# EVK-IRIS-W1_MOD.net
KiCad netlist of a schematic drawn in Altium Designer
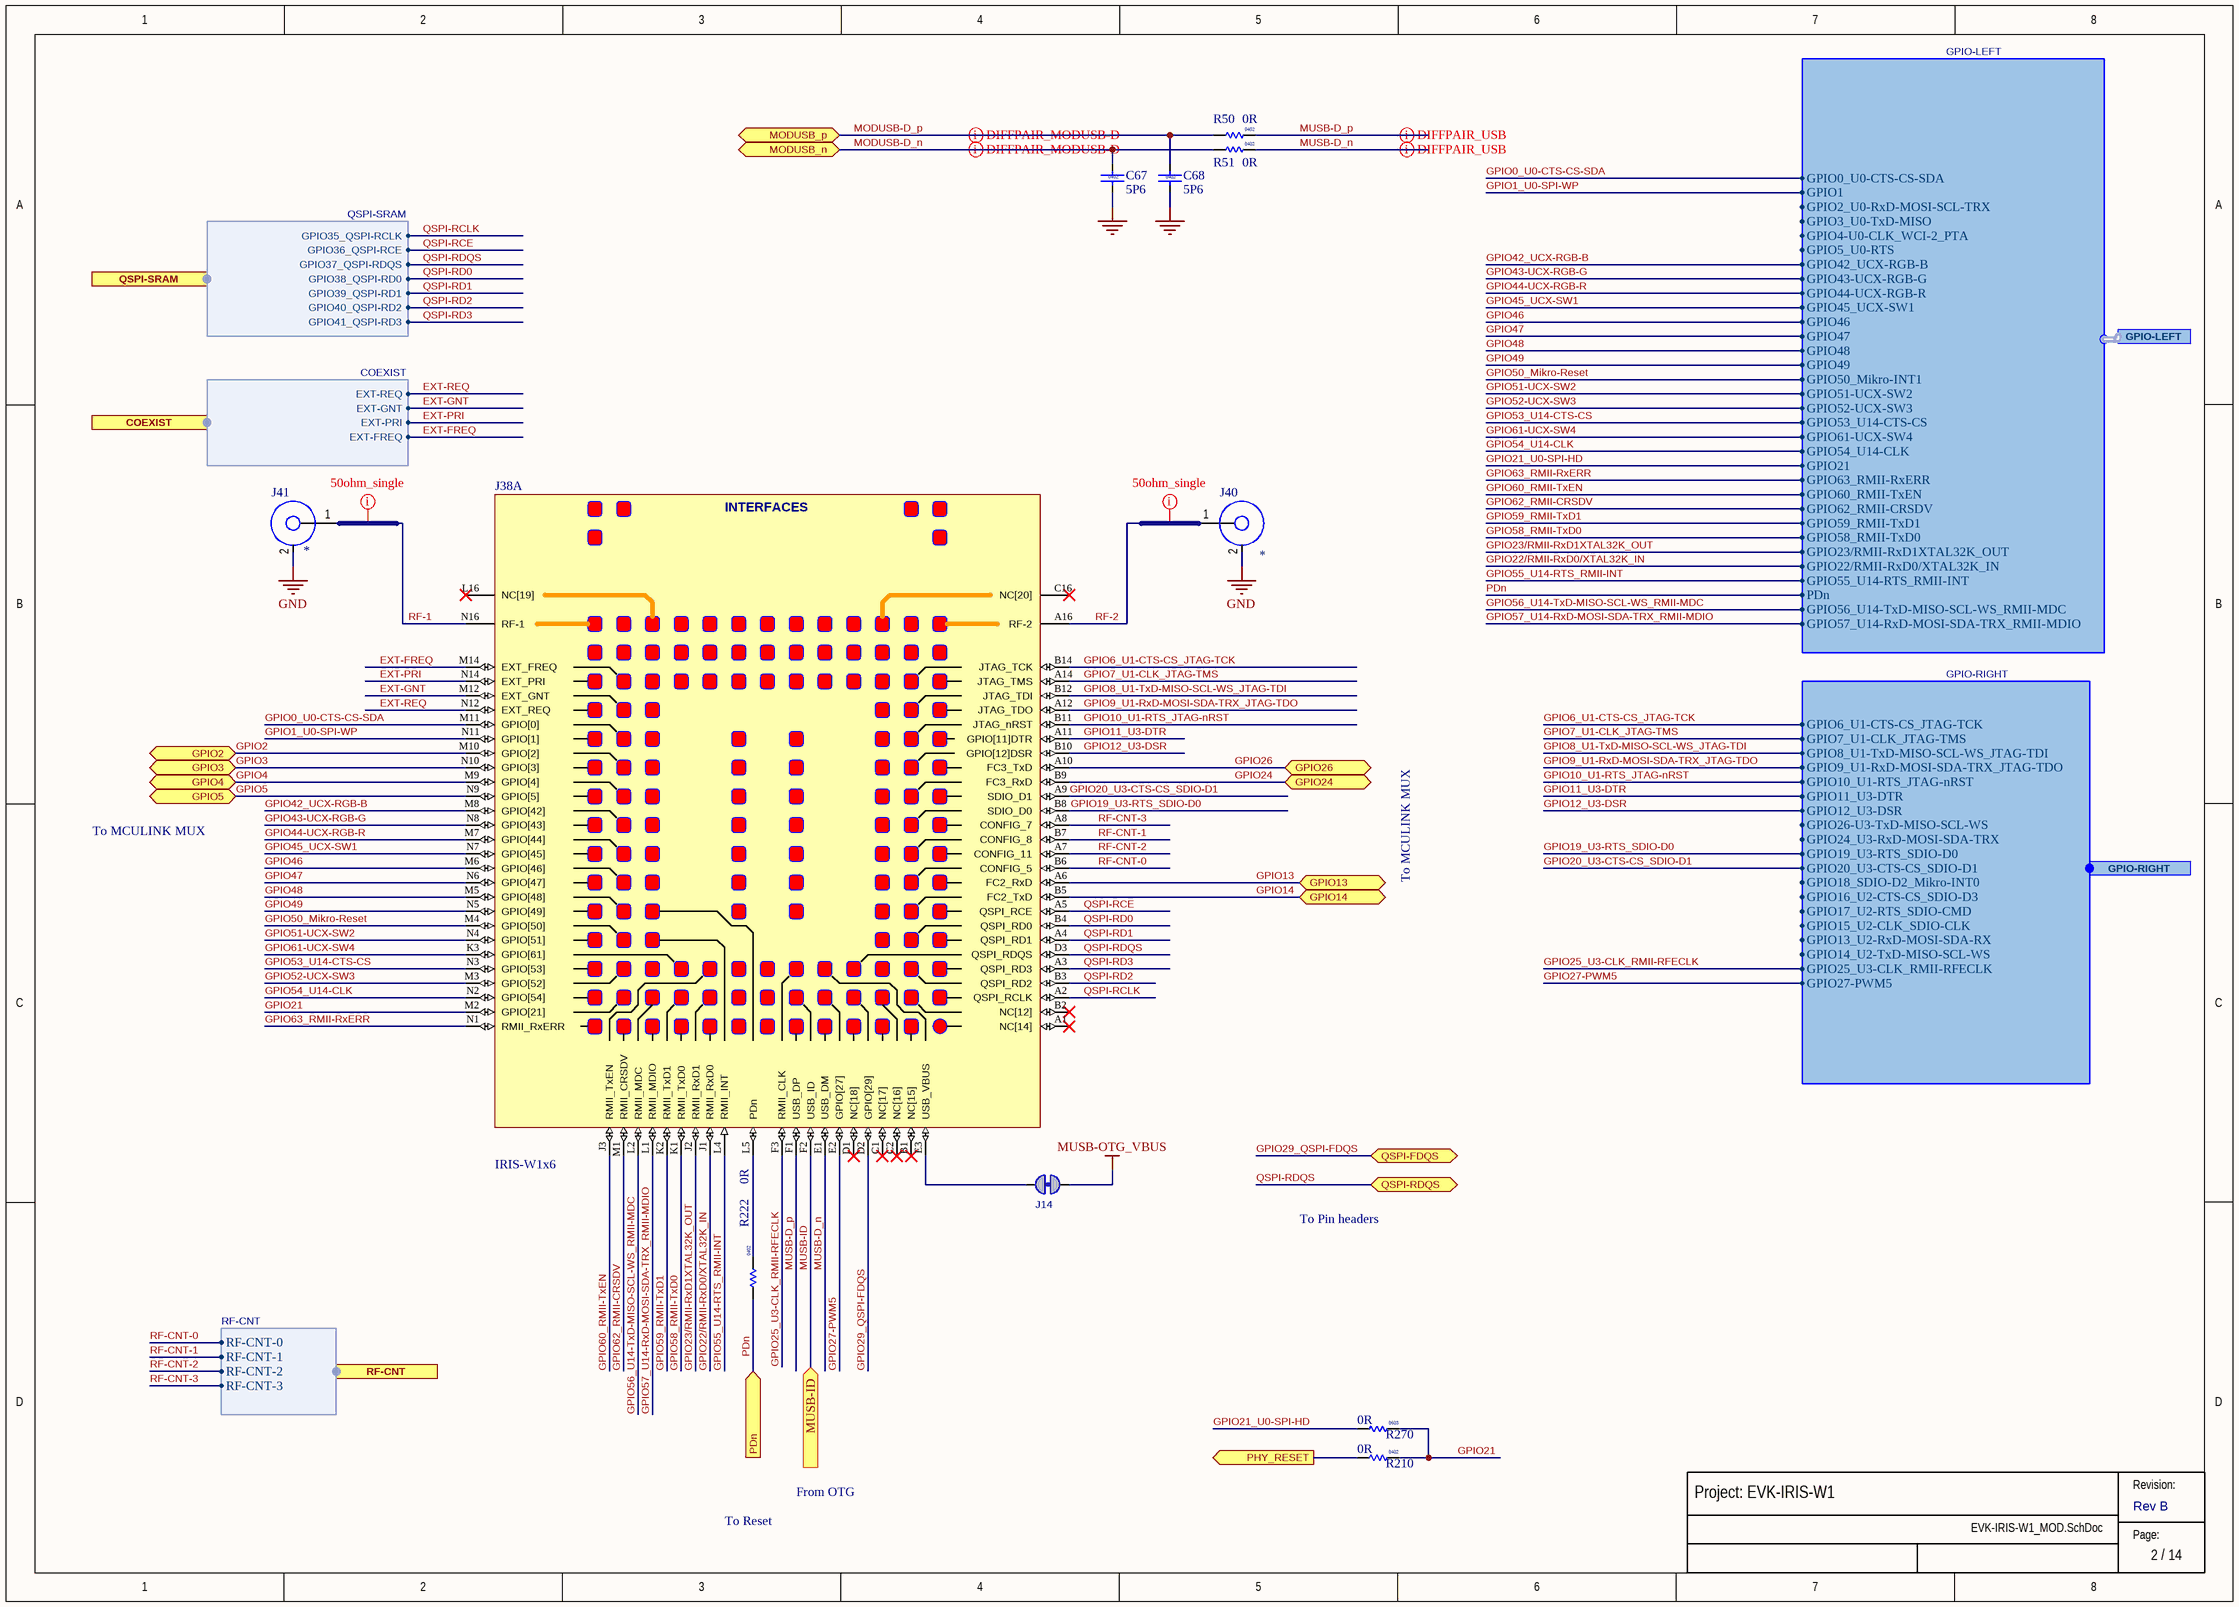
[diagram p0: EVK-IRIS-W1_MOD.SchDoc]

(export (version "E")
  (design (tool "Eeschema 10.0.6"))
  (components
    (comp (ref "C67")
      (value "5P6")
      (footprint "Cap 0402")
      (description "CAP CER C0G 0402 5P6 +/-0.25P 25V")
      (fields
        (field (name "SIZE") "0402")
        (field (name "PART NUMBER") "UBXH01-0004011")
        (field (name "TOLERANCE") "+/-0.25P")
        (field (name "EDITOR") "roland.rust")
        (field (name "RELEASED BY") "roland.rust")
      )
      (libsource (lib "UBX_Parts_DB_Lib") (part "Cap Chip"))
    )
    (comp (ref "C68")
      (value "5P6")
      (footprint "Cap 0402")
      (description "CAP CER C0G 0402 5P6 +/-0.25P 25V")
      (fields
        (field (name "SIZE") "0402")
        (field (name "PART NUMBER") "UBXH01-0004011")
        (field (name "TOLERANCE") "+/-0.25P")
        (field (name "EDITOR") "roland.rust")
        (field (name "RELEASED BY") "roland.rust")
      )
      (libsource (lib "UBX_Parts_DB_Lib") (part "Cap Chip"))
    )
    (comp (ref "J14")
      (value "Solderbridge-ShortDNP")
      (footprint "Solderbridge-Short")
      (description "Solderbridge-Short")
      (fields (field (name "ADDED BY") "Paul B"))
      (libsource (lib "PCB_Misc") (part "Solderbridge-Short"))
    )
    (comp (ref "J38")
      (value "IRIS-W1x6")
      (footprint "IRIS-W1x6_LGA152")
      (description "SHORT RANGE STAND-ALONE MULTIRADIO MODULE U-BLOX IRIS-W106")
      (fields (field (name "PART NUMBER") "UBXH14-0000681") (field (name "EDITOR") "olof.viklund"))
      (libsource (lib "UBX_Parts_DB_Lib") (part "IRIS-W1_152pin"))
    )
    (comp (ref "J40")
      (value "130-00067")
      (footprint "U.FL_3Pin")
      (description "U.FL jack, SMA 50 ohm, 3 pin, SMT")
      (fields (field (name "MANUFACTURER P/N") "*") (field (name "VOLTAGE") "None"))
      (libsource (lib "Arena_Parts_DB_Lib") (part "CON_Coax_2Pin"))
    )
    (comp (ref "J41")
      (value "130-00067")
      (footprint "U.FL_3Pin")
      (description "U.FL jack, SMA 50 ohm, 3 pin, SMT")
      (fields (field (name "MANUFACTURER P/N") "*") (field (name "VOLTAGE") "None"))
      (libsource (lib "Arena_Parts_DB_Lib") (part "CON_Coax_2Pin"))
    )
    (comp (ref "R50")
      (value "0R")
      (footprint "RES 0402 HD")
      (description "RES THICK FILM CHIP 0402 0R 0 100mW")
      (fields
        (field (name "SIZE") "0402")
        (field (name "PART NUMBER") "UBXH18-0003002")
        (field (name "TOLERANCE") "0")
        (field (name "EDITOR") "charlotte.biber")
        (field (name "RELEASED BY") "peter.mueller")
      )
      (libsource (lib "UBX_Parts_DB_Lib") (part "Res sm"))
    )
    (comp (ref "R51")
      (value "0R")
      (footprint "RES 0402 HD")
      (description "RES THICK FILM CHIP 0402 0R 0 100mW")
      (fields
        (field (name "SIZE") "0402")
        (field (name "PART NUMBER") "UBXH18-0003002")
        (field (name "TOLERANCE") "0")
        (field (name "EDITOR") "charlotte.biber")
        (field (name "RELEASED BY") "peter.mueller")
      )
      (libsource (lib "UBX_Parts_DB_Lib") (part "Res sm"))
    )
    (comp (ref "R210")
      (value "0R")
      (footprint "RES 0402 HD")
      (description "RES THICK FILM CHIP 0402 0R 0 100mW")
      (fields
        (field (name "SIZE") "0402")
        (field (name "PART NUMBER") "UBXH18-0003002")
        (field (name "TOLERANCE") "0")
        (field (name "EDITOR") "charlotte.biber")
        (field (name "RELEASED BY") "peter.mueller")
      )
      (libsource (lib "UBX_Parts_DB_Lib") (part "Res sm"))
    )
    (comp (ref "R222")
      (value "0R")
      (footprint "RES 0402 HD")
      (description "RES THICK FILM CHIP 0402 0R 0 100mW")
      (fields
        (field (name "SIZE") "0402")
        (field (name "PART NUMBER") "UBXH18-0003002")
        (field (name "TOLERANCE") "0")
        (field (name "EDITOR") "charlotte.biber")
        (field (name "RELEASED BY") "peter.mueller")
      )
      (libsource (lib "UBX_Parts_DB_Lib") (part "Res sm"))
    )
    (comp (ref "R270")
      (value "0R")
      (footprint "RES 0603 HD")
      (description "RES THICK FILM CHIP 0603 0R 0 100mW")
      (fields
        (field (name "SIZE") "0603")
        (field (name "PART NUMBER") "UBXH18-0003001")
        (field (name "TOLERANCE") "0")
        (field (name "EDITOR") "martin.frauchiger")
        (field (name "RELEASED BY") "martin.frauchiger")
      )
      (libsource (lib "UBX_Parts_DB_Lib") (part "Res sm"))
    )
  )
  (nets
    (net (code "6") (name "/EXT-FREQ") (class "Default")
      (node (ref "J38") (pin "M14") (pinfunction "EXT_FREQ_M14") (pintype "bidirectional"))
    )
    (net (code "7") (name "/EXT-GNT") (class "Default")
      (node (ref "J38") (pin "M12") (pinfunction "EXT_GNT_M12") (pintype "bidirectional"))
    )
    (net (code "8") (name "/EXT-PRI") (class "Default")
      (node (ref "J38") (pin "N14") (pinfunction "EXT_PRI_N14") (pintype "bidirectional"))
    )
    (net (code "9") (name "/EXT-REQ") (class "Default")
      (node (ref "J38") (pin "N12") (pinfunction "EXT_REQ_N12") (pintype "bidirectional"))
    )
    (net (code "10") (name "/GPIO0_U0-CTS-CS-SDA") (class "Default")
      (node (ref "J38") (pin "M11") (pinfunction "GPIO[0]_M11") (pintype "bidirectional"))
    )
    (net (code "11") (name "/GPIO1_U0-SPI-WP") (class "Default")
      (node (ref "J38") (pin "N11") (pinfunction "GPIO[1]_N11") (pintype "bidirectional"))
    )
    (net (code "12") (name "/GPIO2") (class "Default")
      (node (ref "J38") (pin "M10") (pinfunction "GPIO[2]_M10") (pintype "bidirectional"))
    )
    (net (code "13") (name "/GPIO3") (class "Default")
      (node (ref "J38") (pin "N10") (pinfunction "GPIO[3]_N10") (pintype "bidirectional"))
    )
    (net (code "14") (name "/GPIO4") (class "Default")
      (node (ref "J38") (pin "M9") (pinfunction "GPIO[4]_M9") (pintype "bidirectional"))
    )
    (net (code "15") (name "/GPIO5") (class "Default")
      (node (ref "J38") (pin "N9") (pinfunction "GPIO[5]_N9") (pintype "bidirectional"))
    )
    (net (code "16") (name "/GPIO6_U1-CTS-CS_JTAG-TCK") (class "Default")
      (node (ref "J38") (pin "B14") (pinfunction "JTAG_TCK_B14") (pintype "bidirectional"))
    )
    (net (code "17") (name "/GPIO7_U1-CLK_JTAG-TMS") (class "Default")
      (node (ref "J38") (pin "A14") (pinfunction "JTAG_TMS_A14") (pintype "bidirectional"))
    )
    (net (code "18") (name "/GPIO8_U1-TxD-MISO-SCL-WS_JTAG-TDI") (class "Default")
      (node (ref "J38") (pin "B12") (pinfunction "JTAG_TDI_B12") (pintype "bidirectional"))
    )
    (net (code "19") (name "/GPIO9_U1-RxD-MOSI-SDA-TRX_JTAG-TDO") (class "Default")
      (node (ref "J38") (pin "A12") (pinfunction "JTAG_TDO_A12") (pintype "bidirectional"))
    )
    (net (code "20") (name "/GPIO10_U1-RTS_JTAG-nRST") (class "Default")
      (node (ref "J38") (pin "B11") (pinfunction "JTAG_nRST_B11") (pintype "bidirectional"))
    )
    (net (code "21") (name "/GPIO11_U3-DTR") (class "Default")
      (node (ref "J38") (pin "A11") (pinfunction "GPIO[11]DTR_A11") (pintype "bidirectional"))
    )
    (net (code "22") (name "/GPIO12_U3-DSR") (class "Default")
      (node (ref "J38") (pin "B10") (pinfunction "GPIO[12]DSR_B10") (pintype "bidirectional"))
    )
    (net (code "23") (name "/GPIO13") (class "Default")
      (node (ref "J38") (pin "A6") (pinfunction "FC2_RxD_A6") (pintype "bidirectional"))
    )
    (net (code "24") (name "/GPIO14") (class "Default")
      (node (ref "J38") (pin "B5") (pinfunction "FC2_TxD_B5") (pintype "bidirectional"))
    )
    (net (code "25") (name "/GPIO19_U3-RTS_SDIO-D0") (class "Default")
      (node (ref "J38") (pin "B8") (pinfunction "SDIO_D0_B8") (pintype "bidirectional"))
    )
    (net (code "26") (name "/GPIO20_U3-CTS-CS_SDIO-D1") (class "Default")
      (node (ref "J38") (pin "A9") (pinfunction "SDIO_D1_A9") (pintype "bidirectional"))
    )
    (net (code "27") (name "/GPIO21") (class "Default")
      (node (ref "J38") (pin "M2") (pinfunction "GPIO[21]_M2") (pintype "bidirectional"))
      (node (ref "R210") (pin "2") (pinfunction "2_2") (pintype "passive"))
      (node (ref "R270") (pin "2") (pinfunction "2_2") (pintype "passive"))
    )
    (net (code "28") (name "/GPIO21_U0-SPI-HD") (class "Default")
      (node (ref "R270") (pin "1") (pinfunction "1_1") (pintype "passive"))
    )
    (net (code "29") (name "/GPIO22{slash}RMII-RxD0{slash}XTAL32K_IN") (class "Default")
      (node (ref "J38") (pin "J1") (pinfunction "RMII_RxD0_J1") (pintype "bidirectional"))
    )
    (net (code "30") (name "/GPIO23{slash}RMII-RxD1XTAL32K_OUT") (class "Default")
      (node (ref "J38") (pin "J2") (pinfunction "RMII_RxD1_J2") (pintype "bidirectional"))
    )
    (net (code "31") (name "/GPIO24") (class "Default")
      (node (ref "J38") (pin "B9") (pinfunction "FC3_RxD_B9") (pintype "bidirectional"))
    )
    (net (code "32") (name "/GPIO25_U3-CLK_RMII-RFECLK") (class "Default")
      (node (ref "J38") (pin "F3") (pinfunction "RMII_CLK_F3") (pintype "bidirectional"))
    )
    (net (code "33") (name "/GPIO26") (class "Default")
      (node (ref "J38") (pin "A10") (pinfunction "FC3_TxD_A10") (pintype "bidirectional"))
    )
    (net (code "34") (name "/GPIO27-PWM5") (class "Default")
      (node (ref "J38") (pin "E2") (pinfunction "GPIO[27]_E2") (pintype "bidirectional"))
    )
    (net (code "35") (name "/GPIO29_QSPI-FDQS") (class "Default")
      (node (ref "J38") (pin "D2") (pinfunction "GPIO[29]_D2") (pintype "bidirectional"))
    )
    (net (code "36") (name "/GPIO42_UCX-RGB-B") (class "Default")
      (node (ref "J38") (pin "M8") (pinfunction "GPIO[42]_M8") (pintype "bidirectional"))
    )
    (net (code "37") (name "/GPIO43-UCX-RGB-G") (class "Default")
      (node (ref "J38") (pin "N8") (pinfunction "GPIO[43]_N8") (pintype "bidirectional"))
    )
    (net (code "38") (name "/GPIO44-UCX-RGB-R") (class "Default")
      (node (ref "J38") (pin "M7") (pinfunction "GPIO[44]_M7") (pintype "bidirectional"))
    )
    (net (code "39") (name "/GPIO45_UCX-SW1") (class "Default")
      (node (ref "J38") (pin "N7") (pinfunction "GPIO[45]_N7") (pintype "bidirectional"))
    )
    (net (code "40") (name "/GPIO46") (class "Default")
      (node (ref "J38") (pin "M6") (pinfunction "GPIO[46]_M6") (pintype "bidirectional"))
    )
    (net (code "41") (name "/GPIO47") (class "Default")
      (node (ref "J38") (pin "N6") (pinfunction "GPIO[47]_N6") (pintype "bidirectional"))
    )
    (net (code "42") (name "/GPIO48") (class "Default")
      (node (ref "J38") (pin "M5") (pinfunction "GPIO[48]_M5") (pintype "bidirectional"))
    )
    (net (code "43") (name "/GPIO49") (class "Default")
      (node (ref "J38") (pin "N5") (pinfunction "GPIO[49]_N5") (pintype "bidirectional"))
    )
    (net (code "44") (name "/GPIO50_Mikro-Reset") (class "Default")
      (node (ref "J38") (pin "M4") (pinfunction "GPIO[50]_M4") (pintype "bidirectional"))
    )
    (net (code "45") (name "/GPIO51-UCX-SW2") (class "Default")
      (node (ref "J38") (pin "N4") (pinfunction "GPIO[51]_N4") (pintype "bidirectional"))
    )
    (net (code "46") (name "/GPIO52-UCX-SW3") (class "Default")
      (node (ref "J38") (pin "M3") (pinfunction "GPIO[52]_M3") (pintype "bidirectional"))
    )
    (net (code "47") (name "/GPIO53_U14-CTS-CS") (class "Default")
      (node (ref "J38") (pin "N3") (pinfunction "GPIO[53]_N3") (pintype "bidirectional"))
    )
    (net (code "48") (name "/GPIO54_U14-CLK") (class "Default")
      (node (ref "J38") (pin "N2") (pinfunction "GPIO[54]_N2") (pintype "bidirectional"))
    )
    (net (code "49") (name "/GPIO55_U14-RTS_RMII-INT") (class "Default")
      (node (ref "J38") (pin "L4") (pinfunction "RMII_INT_L4") (pintype "input"))
    )
    (net (code "50") (name "/GPIO56_U14-TxD-MISO-SCL-WS_RMII-MDC") (class "Default")
      (node (ref "J38") (pin "L2") (pinfunction "RMII_MDC_L2") (pintype "bidirectional"))
    )
    (net (code "51") (name "/GPIO57_U14-RxD-MOSI-SDA-TRX_RMII-MDIO") (class "Default")
      (node (ref "J38") (pin "L1") (pinfunction "RMII_MDIO_L1") (pintype "bidirectional"))
    )
    (net (code "52") (name "/GPIO58_RMII-TxD0") (class "Default")
      (node (ref "J38") (pin "K1") (pinfunction "RMII_TxD0_K1") (pintype "bidirectional"))
    )
    (net (code "53") (name "/GPIO59_RMII-TxD1") (class "Default")
      (node (ref "J38") (pin "K2") (pinfunction "RMII_TxD1_K2") (pintype "bidirectional"))
    )
    (net (code "54") (name "/GPIO60_RMII-TxEN") (class "Default")
      (node (ref "J38") (pin "J3") (pinfunction "RMII_TxEN_J3") (pintype "bidirectional"))
    )
    (net (code "55") (name "/GPIO61-UCX-SW4") (class "Default")
      (node (ref "J38") (pin "K3") (pinfunction "GPIO[61]_K3") (pintype "bidirectional"))
    )
    (net (code "56") (name "/GPIO62_RMII-CRSDV") (class "Default")
      (node (ref "J38") (pin "M1") (pinfunction "RMII_CRSDV_M1") (pintype "bidirectional"))
    )
    (net (code "57") (name "/GPIO63_RMII-RxERR") (class "Default")
      (node (ref "J38") (pin "N1") (pinfunction "RMII_RxERR_N1") (pintype "bidirectional"))
    )
    (net (code "58") (name "/MODUSB-D_n") (class "Default")
      (node (ref "C67") (pin "1") (pinfunction "1_1") (pintype "passive"))
      (node (ref "R51") (pin "1") (pinfunction "1_1") (pintype "passive"))
    )
    (net (code "59") (name "/MODUSB-D_p") (class "Default")
      (node (ref "C68") (pin "1") (pinfunction "1_1") (pintype "passive"))
      (node (ref "R50") (pin "1") (pinfunction "1_1") (pintype "passive"))
    )
    (net (code "60") (name "/MUSB-D_n") (class "Default")
      (node (ref "J38") (pin "E1") (pinfunction "USB_DM_E1") (pintype "bidirectional"))
      (node (ref "R51") (pin "2") (pinfunction "2_2") (pintype "passive"))
    )
    (net (code "61") (name "/MUSB-D_p") (class "Default")
      (node (ref "J38") (pin "F1") (pinfunction "USB_DP_F1") (pintype "bidirectional"))
      (node (ref "R50") (pin "2") (pinfunction "2_2") (pintype "passive"))
    )
    (net (code "62") (name "/MUSB-ID") (class "Default")
      (node (ref "J38") (pin "F2") (pinfunction "USB_ID_F2") (pintype "bidirectional"))
    )
    (net (code "63") (name "/PDn") (class "Default")
      (node (ref "R222") (pin "1") (pinfunction "1_1") (pintype "passive"))
    )
    (net (code "64") (name "/PHY_RESET") (class "Default")
      (node (ref "R210") (pin "1") (pinfunction "1_1") (pintype "passive"))
    )
    (net (code "65") (name "/QSPI-RCE") (class "Default")
      (node (ref "J38") (pin "A5") (pinfunction "QSPI_RCE_A5") (pintype "bidirectional"))
    )
    (net (code "66") (name "/QSPI-RCLK") (class "Default")
      (node (ref "J38") (pin "A2") (pinfunction "QSPI_RCLK_A2") (pintype "bidirectional"))
    )
    (net (code "67") (name "/QSPI-RD0") (class "Default")
      (node (ref "J38") (pin "B4") (pinfunction "QSPI_RD0_B4") (pintype "bidirectional"))
    )
    (net (code "68") (name "/QSPI-RD1") (class "Default")
      (node (ref "J38") (pin "A4") (pinfunction "QSPI_RD1_A4") (pintype "bidirectional"))
    )
    (net (code "69") (name "/QSPI-RD2") (class "Default")
      (node (ref "J38") (pin "B3") (pinfunction "QSPI_RD2_B3") (pintype "bidirectional"))
    )
    (net (code "70") (name "/QSPI-RD3") (class "Default")
      (node (ref "J38") (pin "A3") (pinfunction "QSPI_RD3_A3") (pintype "bidirectional"))
    )
    (net (code "71") (name "/QSPI-RDQS") (class "Default")
      (node (ref "J38") (pin "D3") (pinfunction "QSPI_RDQS_D3") (pintype "bidirectional"))
    )
    (net (code "72") (name "/RF-1") (class "Default")
      (node (ref "J38") (pin "N16") (pinfunction "RF-1_N16") (pintype "passive"))
      (node (ref "J41") (pin "1") (pinfunction "ANT_1") (pintype "passive"))
    )
    (net (code "73") (name "/RF-2") (class "Default")
      (node (ref "J38") (pin "A16") (pinfunction "RF-2_A16") (pintype "passive"))
      (node (ref "J40") (pin "1") (pinfunction "ANT_1") (pintype "passive"))
    )
    (net (code "74") (name "/RF-CNT-0") (class "Default")
      (node (ref "J38") (pin "B6") (pinfunction "CONFIG_5_B6") (pintype "bidirectional"))
    )
    (net (code "75") (name "/RF-CNT-1") (class "Default")
      (node (ref "J38") (pin "B7") (pinfunction "CONFIG_8_B7") (pintype "bidirectional"))
    )
    (net (code "76") (name "/RF-CNT-2") (class "Default")
      (node (ref "J38") (pin "A7") (pinfunction "CONFIG_11_A7") (pintype "bidirectional"))
    )
    (net (code "77") (name "/RF-CNT-3") (class "Default")
      (node (ref "J38") (pin "A8") (pinfunction "CONFIG_7_A8") (pintype "bidirectional"))
    )
    (net (code "83") (name "GND") (class "Default")
      (node (ref "C67") (pin "2") (pinfunction "2_2") (pintype "passive"))
      (node (ref "C68") (pin "2") (pinfunction "2_2") (pintype "passive"))
      (node (ref "J40") (pin "2") (pinfunction "2_2") (pintype "power_in"))
      (node (ref "J41") (pin "2") (pinfunction "2_2") (pintype "power_in"))
    )
    (net (code "84") (name "MUSB-OTG_VBUS") (class "Default")
      (node (ref "J14") (pin "2") (pinfunction "2_2") (pintype "passive"))
    )
    (net (code "85") (name "Net-(J38A-PDn)") (class "Default")
      (node (ref "J38") (pin "L5") (pinfunction "PDn_L5") (pintype "bidirectional"))
      (node (ref "R222") (pin "2") (pinfunction "2_2") (pintype "passive"))
    )
    (net (code "86") (name "Net-(J38A-USB_VBUS)") (class "Default")
      (node (ref "J14") (pin "1") (pinfunction "1_1") (pintype "passive"))
      (node (ref "J38") (pin "E3") (pinfunction "USB_VBUS_E3") (pintype "bidirectional"))
    )
    (net (code "87") (name "unconnected-(J38A-NC[12]-PadB2)") (class "Default")
      (node (ref "J38") (pin "B2") (pinfunction "NC[12]_B2") (pintype "bidirectional+no_connect"))
    )
    (net (code "88") (name "unconnected-(J38A-NC[14]-PadA1)") (class "Default")
      (node (ref "J38") (pin "A1") (pinfunction "NC[14]_A1") (pintype "bidirectional+no_connect"))
    )
    (net (code "89") (name "unconnected-(J38A-NC[15]-PadB1)") (class "Default")
      (node (ref "J38") (pin "B1") (pinfunction "NC[15]_B1") (pintype "bidirectional+no_connect"))
    )
    (net (code "90") (name "unconnected-(J38A-NC[16]-PadC2)") (class "Default")
      (node (ref "J38") (pin "C2") (pinfunction "NC[16]_C2") (pintype "bidirectional+no_connect"))
    )
    (net (code "91") (name "unconnected-(J38A-NC[17]-PadC1)") (class "Default")
      (node (ref "J38") (pin "C1") (pinfunction "NC[17]_C1") (pintype "bidirectional+no_connect"))
    )
    (net (code "92") (name "unconnected-(J38A-NC[18]-PadD1)") (class "Default")
      (node (ref "J38") (pin "D1") (pinfunction "NC[18]_D1") (pintype "bidirectional+no_connect"))
    )
    (net (code "93") (name "unconnected-(J38A-NC[19]-PadL16)") (class "Default")
      (node (ref "J38") (pin "L16") (pinfunction "NC[19]_L16") (pintype "passive+no_connect"))
    )
    (net (code "94") (name "unconnected-(J38A-NC[20]-PadC16)") (class "Default")
      (node (ref "J38") (pin "C16") (pinfunction "NC[20]_C16") (pintype "passive+no_connect"))
    )
  )
)
